# M310B.net
KiCad netlist of a schematic drawn in EAGLE
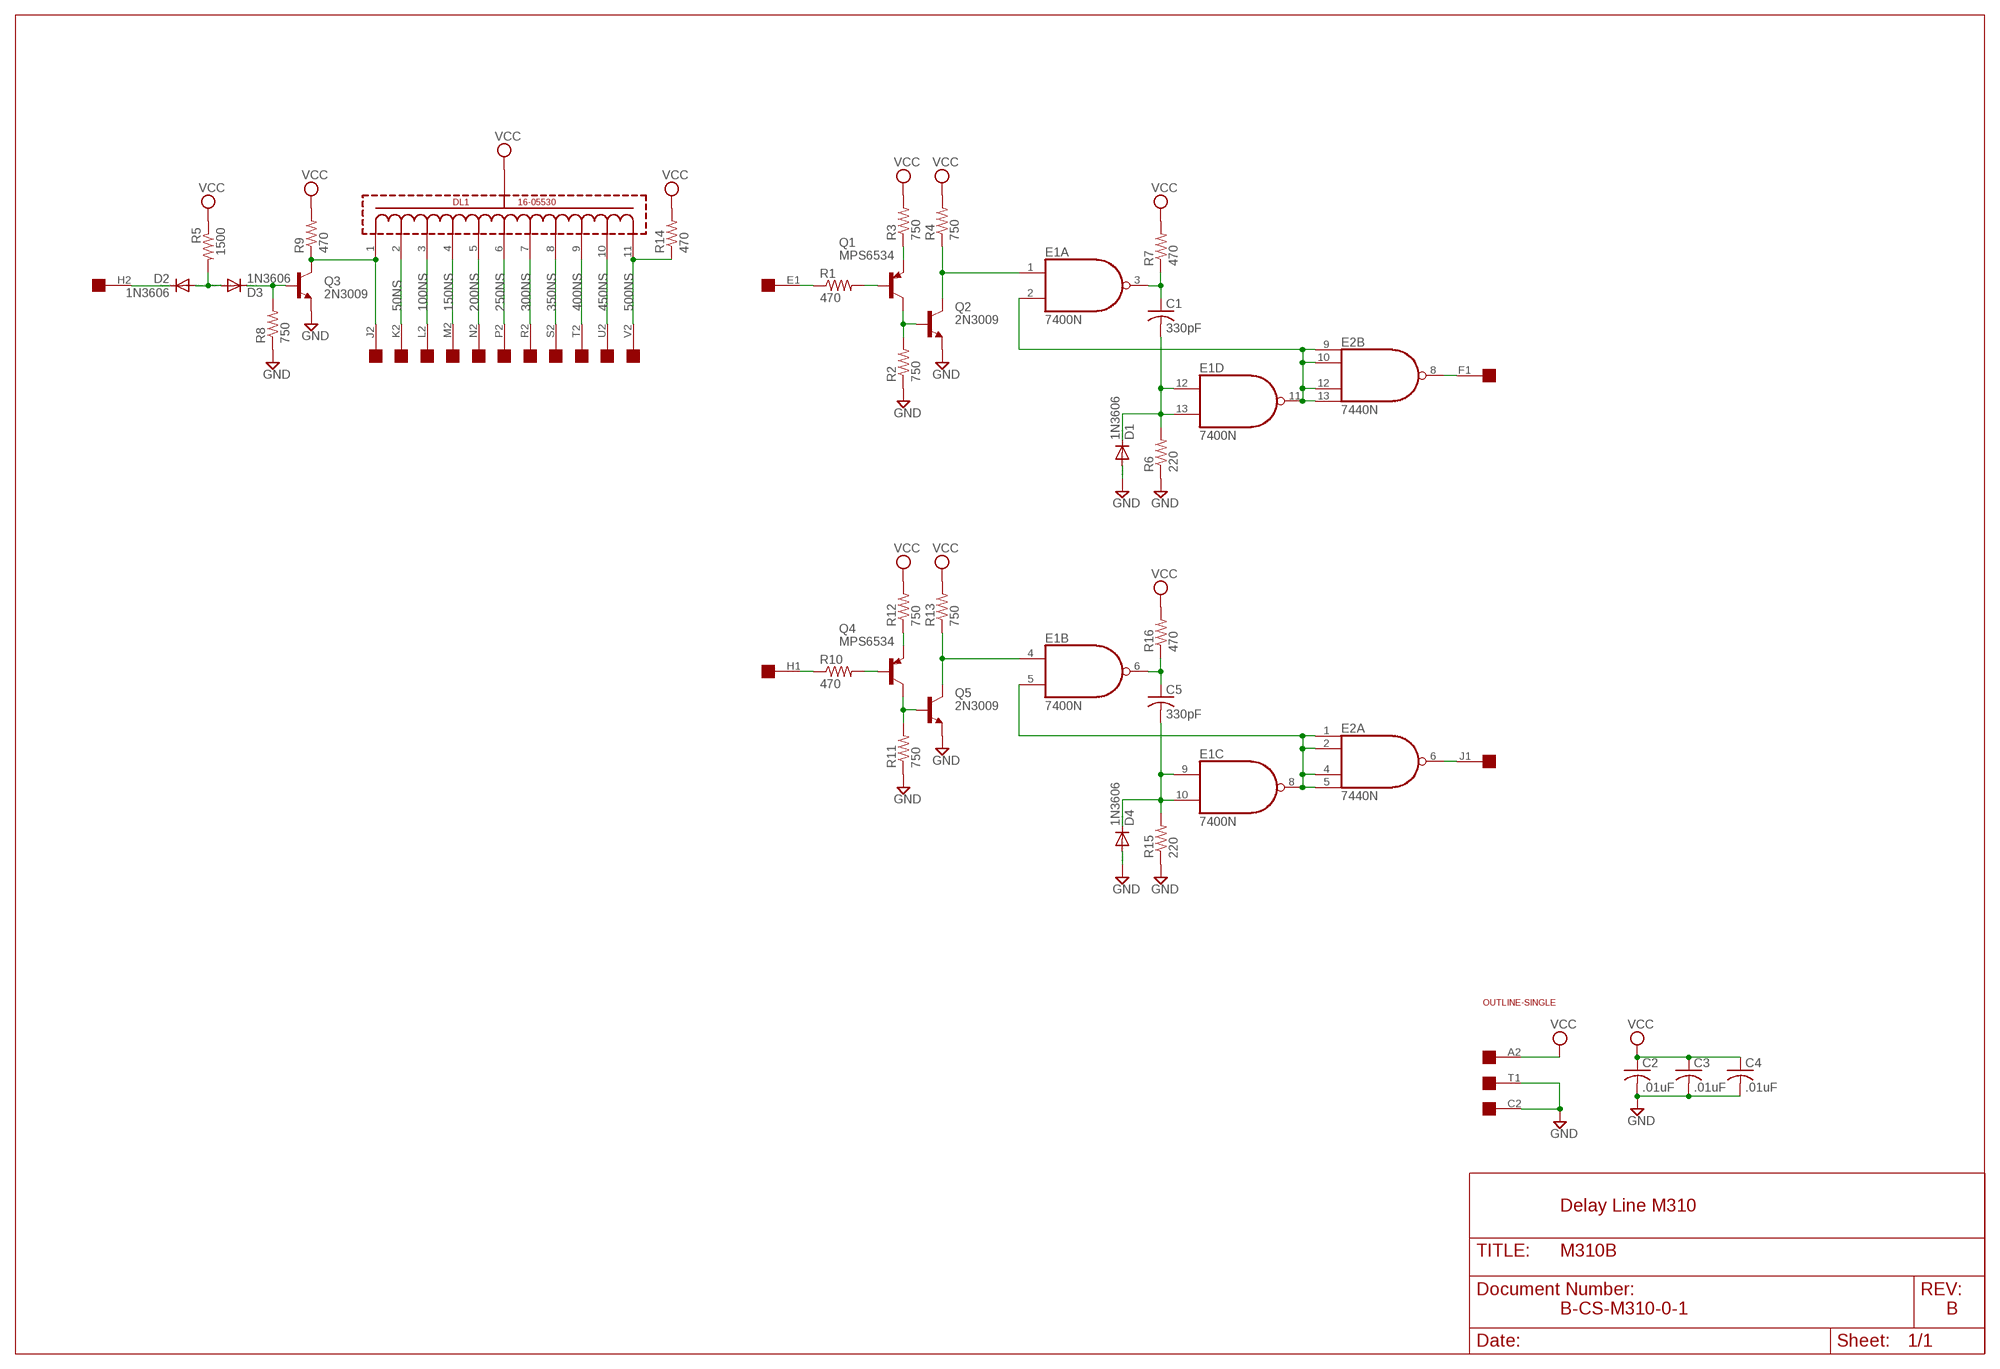
[diagram p0: schematic, sheet 1]

(export (version "E")
  (design (tool "Eeschema 10.0.6"))
  (components
    (comp (ref "C1")
      (value "330pF")
      (footprint "eagle-import:C050-025X075")
      (libsource (lib "eagle-import") (part "C-US050-025X075"))
    )
    (comp (ref "C2")
      (value ".01uF")
      (footprint "eagle-import:C050-025X075")
      (libsource (lib "eagle-import") (part "C-US050-025X075"))
    )
    (comp (ref "C3")
      (value ".01uF")
      (footprint "eagle-import:C050-025X075")
      (libsource (lib "eagle-import") (part "C-US050-025X075"))
    )
    (comp (ref "C4")
      (value ".01uF")
      (footprint "eagle-import:C050-025X075")
      (libsource (lib "eagle-import") (part "C-US050-025X075"))
    )
    (comp (ref "C5")
      (value "330pF")
      (footprint "eagle-import:C050-025X075")
      (libsource (lib "eagle-import") (part "C-US050-025X075"))
    )
    (comp (ref "D1")
      (value "1N3606")
      (footprint "eagle-import:DO35-10")
      (libsource (lib "eagle-import") (part "1N4148DO35-10"))
    )
    (comp (ref "D2")
      (value "1N3606")
      (footprint "eagle-import:DO35-10")
      (libsource (lib "eagle-import") (part "1N4148DO35-10"))
    )
    (comp (ref "D3")
      (value "1N3606")
      (footprint "eagle-import:DO35-10")
      (libsource (lib "eagle-import") (part "1N4148DO35-10"))
    )
    (comp (ref "D4")
      (value "1N3606")
      (footprint "eagle-import:DO35-10")
      (libsource (lib "eagle-import") (part "1N4148DO35-10"))
    )
    (comp (ref "DL1")
      (value "16-05530")
      (footprint "eagle-import:16-05530")
      (libsource (lib "eagle-import") (part "16-05530"))
    )
    (comp (ref "E1")
      (value "7400N")
      (footprint "eagle-import:DIL14")
      (libsource (lib "eagle-import") (part "7400N"))
    )
    (comp (ref "E2")
      (value "7440N")
      (footprint "eagle-import:DIL14")
      (libsource (lib "eagle-import") (part "7440NS"))
    )
    (comp (ref "Q1")
      (value "MPS6534")
      (footprint "eagle-import:TO39")
      (libsource (lib "eagle-import") (part "2N3637"))
    )
    (comp (ref "Q2")
      (value "2N3009")
      (footprint "eagle-import:TO39")
      (libsource (lib "eagle-import") (part "-NPN-TO39-EBC2N3019"))
    )
    (comp (ref "Q3")
      (value "2N3009")
      (footprint "eagle-import:TO39")
      (libsource (lib "eagle-import") (part "-NPN-TO39-EBC2N3019"))
    )
    (comp (ref "Q4")
      (value "MPS6534")
      (footprint "eagle-import:TO39")
      (libsource (lib "eagle-import") (part "2N3637"))
    )
    (comp (ref "Q5")
      (value "2N3009")
      (footprint "eagle-import:TO39")
      (libsource (lib "eagle-import") (part "-NPN-TO39-EBC2N3019"))
    )
    (comp (ref "R1")
      (value "470")
      (footprint "eagle-import:0207_10")
      (libsource (lib "eagle-import") (part "R-US_0207/10"))
    )
    (comp (ref "R2")
      (value "750")
      (footprint "eagle-import:0207_10")
      (libsource (lib "eagle-import") (part "R-US_0207/10"))
    )
    (comp (ref "R3")
      (value "750")
      (footprint "eagle-import:0207_10")
      (libsource (lib "eagle-import") (part "R-US_0207/10"))
    )
    (comp (ref "R4")
      (value "750")
      (footprint "eagle-import:0207_10")
      (libsource (lib "eagle-import") (part "R-US_0207/10"))
    )
    (comp (ref "R5")
      (value "1500")
      (footprint "eagle-import:0207_10")
      (libsource (lib "eagle-import") (part "R-US_0207/10"))
    )
    (comp (ref "R6")
      (value "220")
      (footprint "eagle-import:0207_10")
      (libsource (lib "eagle-import") (part "R-US_0207/10"))
    )
    (comp (ref "R7")
      (value "470")
      (footprint "eagle-import:0207_10")
      (libsource (lib "eagle-import") (part "R-US_0207/10"))
    )
    (comp (ref "R8")
      (value "750")
      (footprint "eagle-import:0207_10")
      (libsource (lib "eagle-import") (part "R-US_0207/10"))
    )
    (comp (ref "R9")
      (value "470")
      (footprint "eagle-import:0207_10")
      (libsource (lib "eagle-import") (part "R-US_0207/10"))
    )
    (comp (ref "R10")
      (value "470")
      (footprint "eagle-import:0207_10")
      (libsource (lib "eagle-import") (part "R-US_0207/10"))
    )
    (comp (ref "R11")
      (value "750")
      (footprint "eagle-import:0207_10")
      (libsource (lib "eagle-import") (part "R-US_0207/10"))
    )
    (comp (ref "R12")
      (value "750")
      (footprint "eagle-import:0207_10")
      (libsource (lib "eagle-import") (part "R-US_0207/10"))
    )
    (comp (ref "R13")
      (value "750")
      (footprint "eagle-import:0207_10")
      (libsource (lib "eagle-import") (part "R-US_0207/10"))
    )
    (comp (ref "R14")
      (value "470")
      (footprint "eagle-import:0207_10")
      (libsource (lib "eagle-import") (part "R-US_0207/10"))
    )
    (comp (ref "R15")
      (value "220")
      (footprint "eagle-import:0207_10")
      (libsource (lib "eagle-import") (part "R-US_0207/10"))
    )
    (comp (ref "R16")
      (value "470")
      (footprint "eagle-import:0207_10")
      (libsource (lib "eagle-import") (part "R-US_0207/10"))
    )
    (comp (ref "U$1")
      (value "OUTLINE-SINGLE")
      (footprint "eagle-import:SINGLE")
      (libsource (lib "eagle-import") (part "OUTLINE-SINGLE"))
    )
    (comp (ref "U$4")
      (value "SINGLE")
      (footprint "eagle-import:EDGE-CON2")
      (libsource (lib "eagle-import") (part "SINGLE"))
    )
  )
  (nets
    (net (code "1") (name "/50NS") (class "Default")
      (node (ref "DL1") (pin "2") (pinfunction "5_2") (pintype "passive"))
      (node (ref "U$4") (pin "K2") (pinfunction "1_K2") (pintype "bidirectional"))
    )
    (net (code "2") (name "/100NS") (class "Default")
      (node (ref "DL1") (pin "3") (pinfunction "10_3") (pintype "passive"))
      (node (ref "U$4") (pin "L2") (pinfunction "1_L2") (pintype "bidirectional"))
    )
    (net (code "3") (name "/150NS") (class "Default")
      (node (ref "DL1") (pin "4") (pinfunction "15_4") (pintype "passive"))
      (node (ref "U$4") (pin "M2") (pinfunction "1_M2") (pintype "bidirectional"))
    )
    (net (code "4") (name "/200NS") (class "Default")
      (node (ref "DL1") (pin "5") (pinfunction "20_5") (pintype "passive"))
      (node (ref "U$4") (pin "N2") (pinfunction "1_N2") (pintype "bidirectional"))
    )
    (net (code "5") (name "/250NS") (class "Default")
      (node (ref "DL1") (pin "6") (pinfunction "25_6") (pintype "passive"))
      (node (ref "U$4") (pin "P2") (pinfunction "1_P2") (pintype "bidirectional"))
    )
    (net (code "6") (name "/300NS") (class "Default")
      (node (ref "DL1") (pin "7") (pinfunction "30_7") (pintype "passive"))
      (node (ref "U$4") (pin "R2") (pinfunction "1_R2") (pintype "bidirectional"))
    )
    (net (code "7") (name "/350NS") (class "Default")
      (node (ref "DL1") (pin "8") (pinfunction "35_8") (pintype "passive"))
      (node (ref "U$4") (pin "S2") (pinfunction "1_S2") (pintype "bidirectional"))
    )
    (net (code "8") (name "/400NS") (class "Default")
      (node (ref "DL1") (pin "9") (pinfunction "40_9") (pintype "passive"))
      (node (ref "U$4") (pin "T2") (pinfunction "1_T2") (pintype "bidirectional"))
    )
    (net (code "9") (name "/450NS") (class "Default")
      (node (ref "DL1") (pin "10") (pinfunction "45_10") (pintype "passive"))
      (node (ref "U$4") (pin "U2") (pinfunction "1_U2") (pintype "bidirectional"))
    )
    (net (code "10") (name "/500NS") (class "Default")
      (node (ref "DL1") (pin "11") (pinfunction "50_11") (pintype "passive"))
      (node (ref "R14") (pin "1") (pinfunction "1_1") (pintype "passive"))
      (node (ref "U$4") (pin "V2") (pinfunction "1_V2") (pintype "bidirectional"))
    )
    (net (code "11") (name "GND") (class "Default")
      (node (ref "C2") (pin "2") (pinfunction "2_2") (pintype "passive"))
      (node (ref "C3") (pin "2") (pinfunction "2_2") (pintype "passive"))
      (node (ref "C4") (pin "2") (pinfunction "2_2") (pintype "passive"))
      (node (ref "D1") (pin "A") (pinfunction "A_A") (pintype "passive"))
      (node (ref "D4") (pin "A") (pinfunction "A_A") (pintype "passive"))
      (node (ref "Q2") (pin "1") (pinfunction "E_1") (pintype "passive"))
      (node (ref "Q3") (pin "1") (pinfunction "E_1") (pintype "passive"))
      (node (ref "Q5") (pin "1") (pinfunction "E_1") (pintype "passive"))
      (node (ref "R11") (pin "1") (pinfunction "1_1") (pintype "passive"))
      (node (ref "R15") (pin "1") (pinfunction "1_1") (pintype "passive"))
      (node (ref "R2") (pin "1") (pinfunction "1_1") (pintype "passive"))
      (node (ref "R6") (pin "1") (pinfunction "1_1") (pintype "passive"))
      (node (ref "R8") (pin "1") (pinfunction "1_1") (pintype "passive"))
      (node (ref "U$4") (pin "C2") (pinfunction "1_C2") (pintype "bidirectional"))
      (node (ref "U$4") (pin "T1") (pinfunction "1_T1") (pintype "bidirectional"))
    )
    (net (code "12") (name "Net-(D2-PadA)") (class "Default")
      (node (ref "D2") (pin "A") (pinfunction "A_A") (pintype "passive"))
      (node (ref "D3") (pin "A") (pinfunction "A_A") (pintype "passive"))
      (node (ref "R5") (pin "2") (pinfunction "2_2") (pintype "passive"))
    )
    (net (code "13") (name "Net-(DL1-0)") (class "Default")
      (node (ref "DL1") (pin "1") (pinfunction "0_1") (pintype "passive"))
      (node (ref "Q3") (pin "3") (pinfunction "C_3") (pintype "passive"))
      (node (ref "R9") (pin "1") (pinfunction "1_1") (pintype "passive"))
      (node (ref "U$4") (pin "J2") (pinfunction "1_J2") (pintype "bidirectional"))
    )
    (net (code "14") (name "Net-(E1A-I0)") (class "Default")
      (node (ref "E1") (pin "1") (pinfunction "I0_1") (pintype "input"))
      (node (ref "Q2") (pin "3") (pinfunction "C_3") (pintype "passive"))
      (node (ref "R4") (pin "1") (pinfunction "1_1") (pintype "passive"))
    )
    (net (code "15") (name "Net-(E1A-I1)") (class "Default")
      (node (ref "E1") (pin "11") (pinfunction "O_11") (pintype "output"))
      (node (ref "E1") (pin "2") (pinfunction "I1_2") (pintype "input"))
      (node (ref "E2") (pin "10") (pinfunction "I1_10") (pintype "input"))
      (node (ref "E2") (pin "12") (pinfunction "I2_12") (pintype "input"))
      (node (ref "E2") (pin "13") (pinfunction "I3_13") (pintype "input"))
      (node (ref "E2") (pin "9") (pinfunction "I0_9") (pintype "input"))
    )
    (net (code "16") (name "Net-(E1A-O)") (class "Default")
      (node (ref "C1") (pin "1") (pinfunction "1_1") (pintype "passive"))
      (node (ref "E1") (pin "3") (pinfunction "O_3") (pintype "output"))
      (node (ref "R7") (pin "1") (pinfunction "1_1") (pintype "passive"))
    )
    (net (code "17") (name "Net-(E1B-I0)") (class "Default")
      (node (ref "E1") (pin "4") (pinfunction "I0_4") (pintype "input"))
      (node (ref "Q5") (pin "3") (pinfunction "C_3") (pintype "passive"))
      (node (ref "R13") (pin "1") (pinfunction "1_1") (pintype "passive"))
    )
    (net (code "18") (name "Net-(E1B-I1)") (class "Default")
      (node (ref "E1") (pin "5") (pinfunction "I1_5") (pintype "input"))
      (node (ref "E1") (pin "8") (pinfunction "O_8") (pintype "output"))
      (node (ref "E2") (pin "1") (pinfunction "I0_1") (pintype "input"))
      (node (ref "E2") (pin "2") (pinfunction "I1_2") (pintype "input"))
      (node (ref "E2") (pin "4") (pinfunction "I2_4") (pintype "input"))
      (node (ref "E2") (pin "5") (pinfunction "I3_5") (pintype "input"))
    )
    (net (code "19") (name "Net-(E1B-O)") (class "Default")
      (node (ref "C5") (pin "1") (pinfunction "1_1") (pintype "passive"))
      (node (ref "E1") (pin "6") (pinfunction "O_6") (pintype "output"))
      (node (ref "R16") (pin "1") (pinfunction "1_1") (pintype "passive"))
    )
    (net (code "20") (name "Net-(E1C-I0)") (class "Default")
      (node (ref "C5") (pin "2") (pinfunction "2_2") (pintype "passive"))
      (node (ref "D4") (pin "C") (pinfunction "C_C") (pintype "passive"))
      (node (ref "E1") (pin "10") (pinfunction "I1_10") (pintype "input"))
      (node (ref "E1") (pin "9") (pinfunction "I0_9") (pintype "input"))
      (node (ref "R15") (pin "2") (pinfunction "2_2") (pintype "passive"))
    )
    (net (code "21") (name "Net-(E1D-I0)") (class "Default")
      (node (ref "C1") (pin "2") (pinfunction "2_2") (pintype "passive"))
      (node (ref "D1") (pin "C") (pinfunction "C_C") (pintype "passive"))
      (node (ref "E1") (pin "12") (pinfunction "I0_12") (pintype "input"))
      (node (ref "E1") (pin "13") (pinfunction "I1_13") (pintype "input"))
      (node (ref "R6") (pin "2") (pinfunction "2_2") (pintype "passive"))
    )
    (net (code "22") (name "Net-(E2C-O)") (class "Default")
      (node (ref "E2") (pin "6") (pinfunction "O_6") (pintype "output"))
      (node (ref "U$4") (pin "J1") (pinfunction "1_J1") (pintype "bidirectional"))
    )
    (net (code "23") (name "Net-(E2D-O)") (class "Default")
      (node (ref "E2") (pin "8") (pinfunction "O_8") (pintype "output"))
      (node (ref "U$4") (pin "F1") (pinfunction "1_F1") (pintype "bidirectional"))
    )
    (net (code "24") (name "Net-(Q1-B)") (class "Default")
      (node (ref "Q1") (pin "2") (pinfunction "B_2") (pintype "passive"))
      (node (ref "R1") (pin "2") (pinfunction "2_2") (pintype "passive"))
    )
    (net (code "25") (name "Net-(Q1-C)") (class "Default")
      (node (ref "Q1") (pin "3") (pinfunction "C_3") (pintype "passive"))
      (node (ref "Q2") (pin "2") (pinfunction "B_2") (pintype "passive"))
      (node (ref "R2") (pin "2") (pinfunction "2_2") (pintype "passive"))
    )
    (net (code "26") (name "Net-(Q1-E)") (class "Default")
      (node (ref "Q1") (pin "1") (pinfunction "E_1") (pintype "passive"))
      (node (ref "R3") (pin "1") (pinfunction "1_1") (pintype "passive"))
    )
    (net (code "27") (name "Net-(Q3-B)") (class "Default")
      (node (ref "D3") (pin "C") (pinfunction "C_C") (pintype "passive"))
      (node (ref "Q3") (pin "2") (pinfunction "B_2") (pintype "passive"))
      (node (ref "R8") (pin "2") (pinfunction "2_2") (pintype "passive"))
    )
    (net (code "28") (name "Net-(Q4-B)") (class "Default")
      (node (ref "Q4") (pin "2") (pinfunction "B_2") (pintype "passive"))
      (node (ref "R10") (pin "2") (pinfunction "2_2") (pintype "passive"))
    )
    (net (code "29") (name "Net-(Q4-C)") (class "Default")
      (node (ref "Q4") (pin "3") (pinfunction "C_3") (pintype "passive"))
      (node (ref "Q5") (pin "2") (pinfunction "B_2") (pintype "passive"))
      (node (ref "R11") (pin "2") (pinfunction "2_2") (pintype "passive"))
    )
    (net (code "30") (name "Net-(Q4-E)") (class "Default")
      (node (ref "Q4") (pin "1") (pinfunction "E_1") (pintype "passive"))
      (node (ref "R12") (pin "1") (pinfunction "1_1") (pintype "passive"))
    )
    (net (code "31") (name "Net-(U$4I-1)") (class "Default")
      (node (ref "R1") (pin "1") (pinfunction "1_1") (pintype "passive"))
      (node (ref "U$4") (pin "E1") (pinfunction "1_E1") (pintype "bidirectional"))
    )
    (net (code "32") (name "Net-(U$4M-1)") (class "Default")
      (node (ref "R10") (pin "1") (pinfunction "1_1") (pintype "passive"))
      (node (ref "U$4") (pin "H1") (pinfunction "1_H1") (pintype "bidirectional"))
    )
    (net (code "33") (name "Net-(U$4N-1)") (class "Default")
      (node (ref "D2") (pin "C") (pinfunction "C_C") (pintype "passive"))
      (node (ref "U$4") (pin "H2") (pinfunction "1_H2") (pintype "bidirectional"))
    )
    (net (code "34") (name "VCC") (class "Default")
      (node (ref "C2") (pin "1") (pinfunction "1_1") (pintype "passive"))
      (node (ref "C3") (pin "1") (pinfunction "1_1") (pintype "passive"))
      (node (ref "C4") (pin "1") (pinfunction "1_1") (pintype "passive"))
      (node (ref "DL1") (pin "12") (pinfunction "GND_12") (pintype "passive"))
      (node (ref "R12") (pin "2") (pinfunction "2_2") (pintype "passive"))
      (node (ref "R13") (pin "2") (pinfunction "2_2") (pintype "passive"))
      (node (ref "R14") (pin "2") (pinfunction "2_2") (pintype "passive"))
      (node (ref "R16") (pin "2") (pinfunction "2_2") (pintype "passive"))
      (node (ref "R3") (pin "2") (pinfunction "2_2") (pintype "passive"))
      (node (ref "R4") (pin "2") (pinfunction "2_2") (pintype "passive"))
      (node (ref "R5") (pin "1") (pinfunction "1_1") (pintype "passive"))
      (node (ref "R7") (pin "2") (pinfunction "2_2") (pintype "passive"))
      (node (ref "R9") (pin "2") (pinfunction "2_2") (pintype "passive"))
      (node (ref "U$4") (pin "A2") (pinfunction "1_A2") (pintype "bidirectional"))
    )
  )
)
